# design1.net
KiCad netlist of a schematic drawn in EAGLE
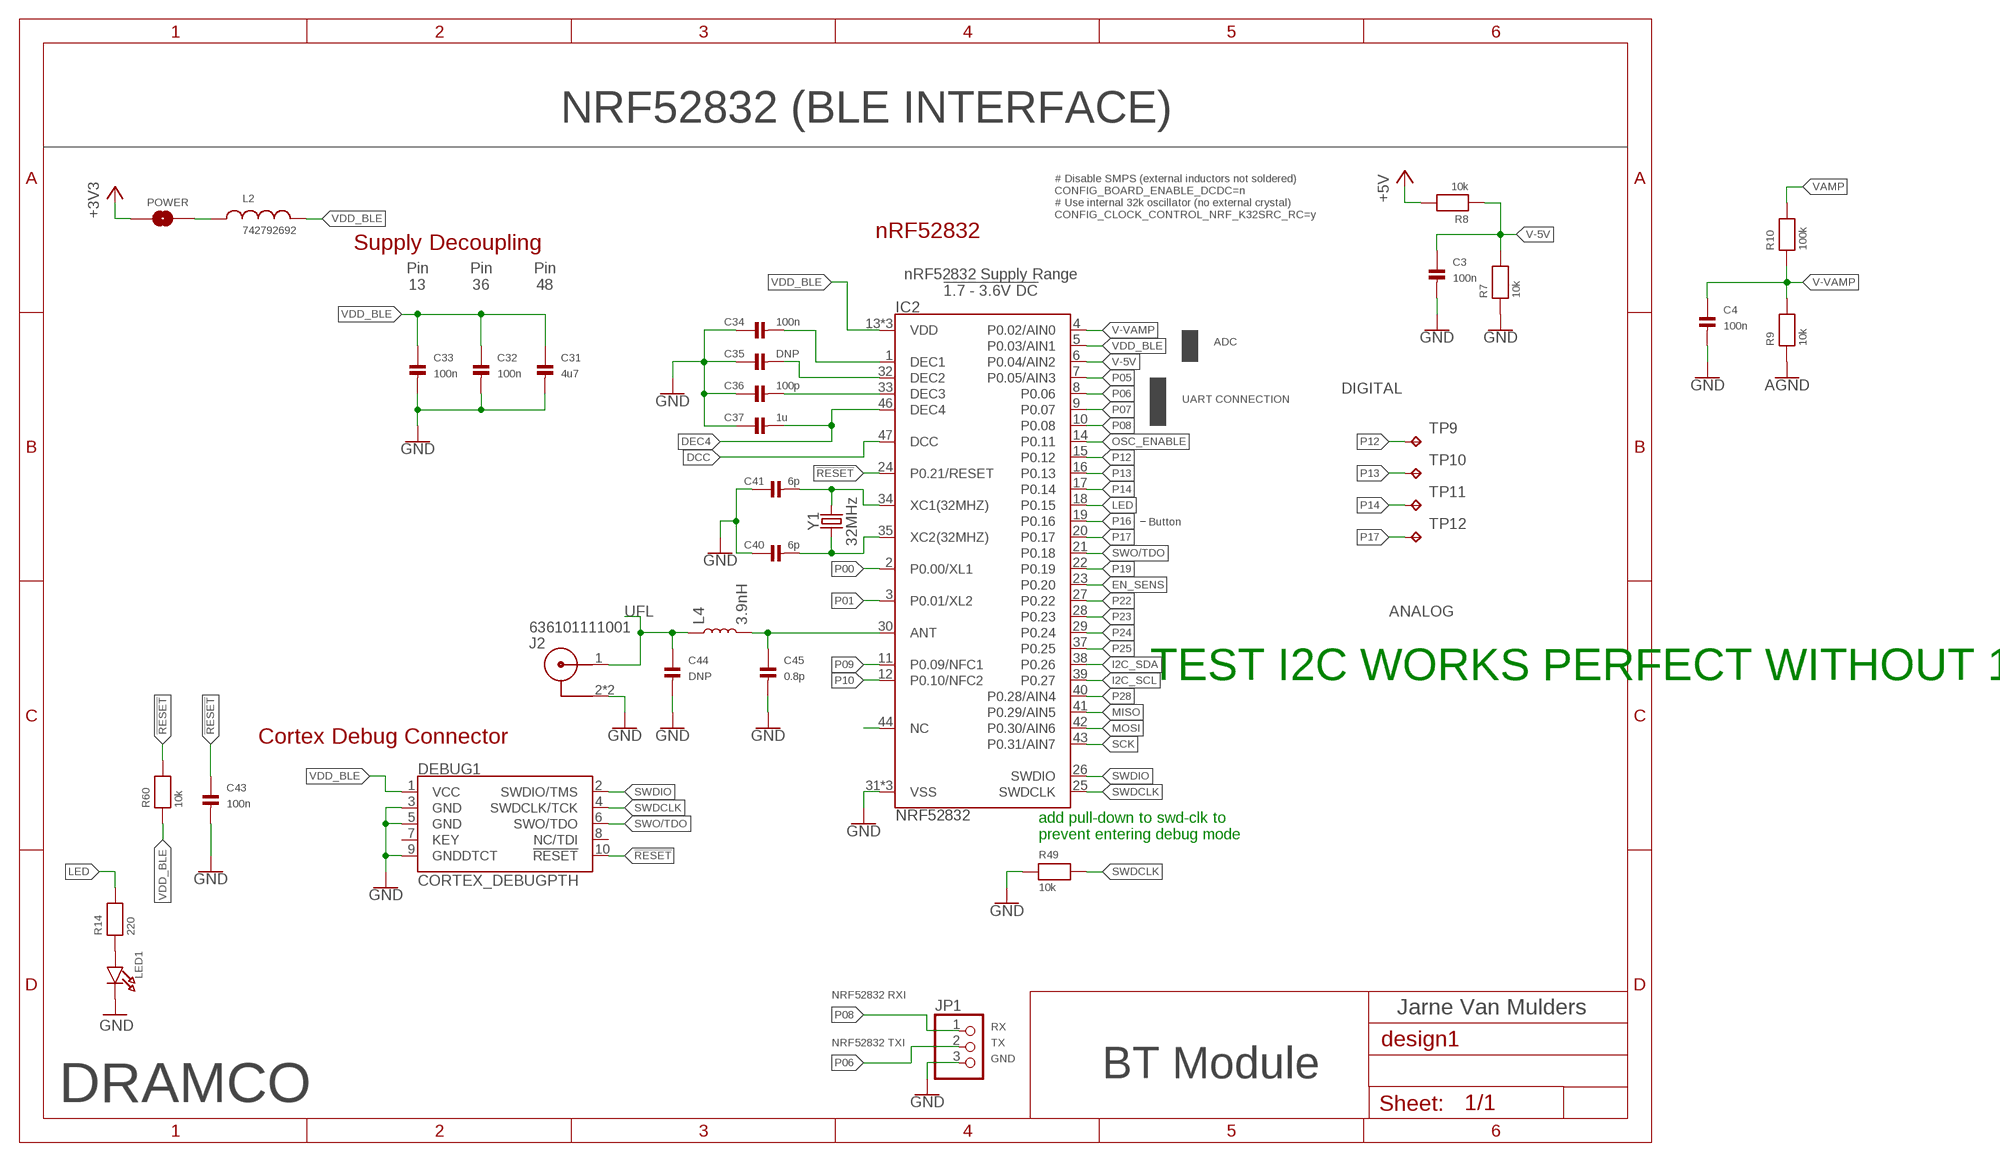
[diagram p0: schematic, sheet 1, part 1 of 2]
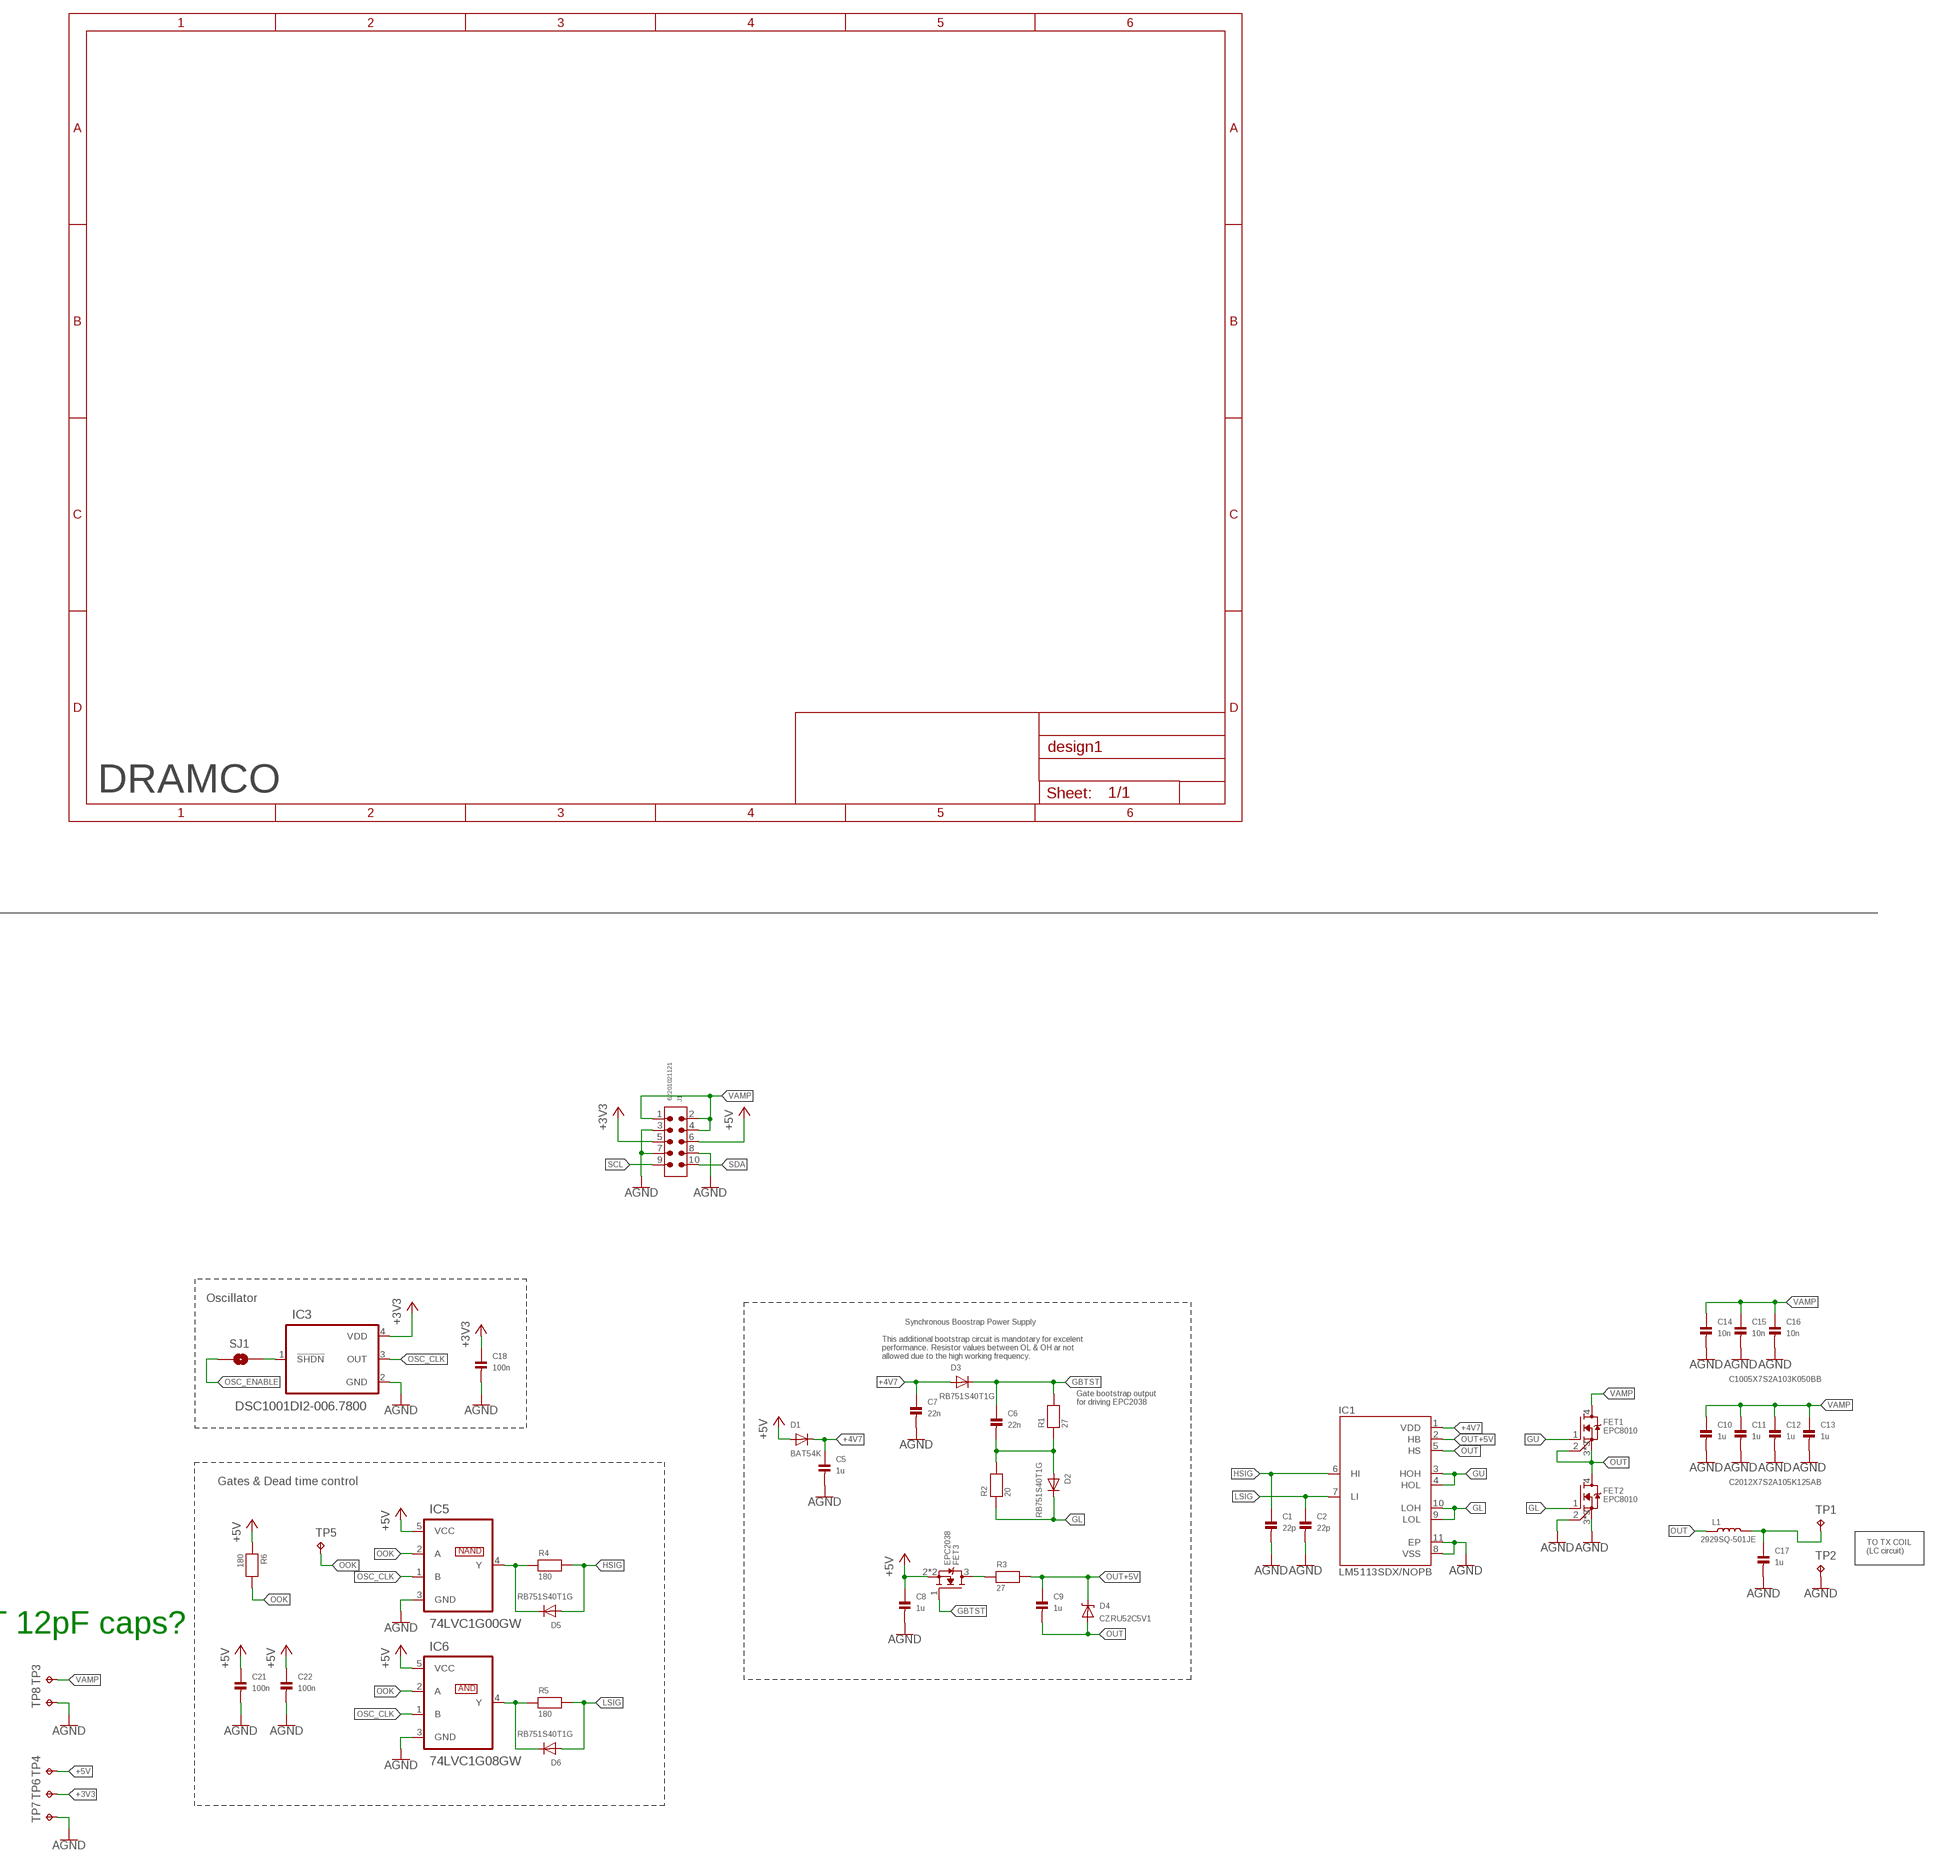
[diagram p1: schematic, sheet 1, part 2 of 2]

(export (version "E")
  (design (tool "Eeschema 10.0.6"))
  (components
    (comp (ref "C1")
      (value "22p")
      (footprint "eagle-import:0402")
      (libsource (lib "eagle-import") (part "CAP_CERAMIC0402"))
    )
    (comp (ref "C2")
      (value "22p")
      (footprint "eagle-import:0402")
      (libsource (lib "eagle-import") (part "CAP_CERAMIC0402"))
    )
    (comp (ref "C3")
      (value "100n")
      (footprint "eagle-import:0402")
      (libsource (lib "eagle-import") (part "CAP_CERAMIC0402"))
    )
    (comp (ref "C4")
      (value "100n")
      (footprint "eagle-import:0402")
      (libsource (lib "eagle-import") (part "CAP_CERAMIC0402"))
    )
    (comp (ref "C5")
      (value "1u")
      (footprint "eagle-import:0402")
      (libsource (lib "eagle-import") (part "CAP_CERAMIC0402"))
    )
    (comp (ref "C6")
      (value "22n")
      (footprint "eagle-import:0402")
      (libsource (lib "eagle-import") (part "CAP_CERAMIC0402"))
    )
    (comp (ref "C7")
      (value "22n")
      (footprint "eagle-import:0402")
      (libsource (lib "eagle-import") (part "CAP_CERAMIC0402"))
    )
    (comp (ref "C8")
      (value "1u")
      (footprint "eagle-import:0402")
      (libsource (lib "eagle-import") (part "CAP_CERAMIC0402"))
    )
    (comp (ref "C9")
      (value "1u")
      (footprint "eagle-import:0402")
      (libsource (lib "eagle-import") (part "CAP_CERAMIC0402"))
    )
    (comp (ref "C10")
      (value "1u")
      (footprint "eagle-import:0805")
      (libsource (lib "eagle-import") (part "CAP_CERAMIC0805"))
    )
    (comp (ref "C11")
      (value "1u")
      (footprint "eagle-import:0805")
      (libsource (lib "eagle-import") (part "CAP_CERAMIC0805"))
    )
    (comp (ref "C12")
      (value "1u")
      (footprint "eagle-import:0805")
      (libsource (lib "eagle-import") (part "CAP_CERAMIC0805"))
    )
    (comp (ref "C13")
      (value "1u")
      (footprint "eagle-import:0805")
      (libsource (lib "eagle-import") (part "CAP_CERAMIC0805"))
    )
    (comp (ref "C14")
      (value "10n")
      (footprint "eagle-import:0402")
      (libsource (lib "eagle-import") (part "CAP_CERAMIC0402"))
    )
    (comp (ref "C15")
      (value "10n")
      (footprint "eagle-import:0402")
      (libsource (lib "eagle-import") (part "CAP_CERAMIC0402"))
    )
    (comp (ref "C16")
      (value "10n")
      (footprint "eagle-import:0402")
      (libsource (lib "eagle-import") (part "CAP_CERAMIC0402"))
    )
    (comp (ref "C17")
      (value "1u")
      (footprint "eagle-import:0805")
      (libsource (lib "eagle-import") (part "CAP_CERAMIC0805"))
    )
    (comp (ref "C18")
      (value "100n")
      (footprint "eagle-import:0603")
      (libsource (lib "eagle-import") (part "CAP_CERAMIC0603"))
    )
    (comp (ref "C21")
      (value "100n")
      (footprint "eagle-import:0402")
      (libsource (lib "eagle-import") (part "CAP_CERAMIC0402"))
    )
    (comp (ref "C22")
      (value "100n")
      (footprint "eagle-import:0402")
      (libsource (lib "eagle-import") (part "CAP_CERAMIC0402"))
    )
    (comp (ref "C31")
      (value "4u7")
      (footprint "eagle-import:0603")
      (libsource (lib "eagle-import") (part "CAP_CERAMIC0603"))
    )
    (comp (ref "C32")
      (value "100n")
      (footprint "eagle-import:0402")
      (libsource (lib "eagle-import") (part "CAP_CERAMIC0402"))
    )
    (comp (ref "C33")
      (value "100n")
      (footprint "eagle-import:0402")
      (libsource (lib "eagle-import") (part "CAP_CERAMIC0402"))
    )
    (comp (ref "C34")
      (value "100n")
      (footprint "eagle-import:0402")
      (libsource (lib "eagle-import") (part "CAP_CERAMIC0402"))
    )
    (comp (ref "C35")
      (value "DNP")
      (footprint "eagle-import:0402")
      (libsource (lib "eagle-import") (part "CAP_CERAMIC0402"))
    )
    (comp (ref "C36")
      (value "100p")
      (footprint "eagle-import:0402")
      (libsource (lib "eagle-import") (part "CAP_CERAMIC0402"))
    )
    (comp (ref "C37")
      (value "1u")
      (footprint "eagle-import:0402")
      (libsource (lib "eagle-import") (part "CAP_CERAMIC0402"))
    )
    (comp (ref "C40")
      (value "6p")
      (footprint "eagle-import:0402")
      (libsource (lib "eagle-import") (part "CAP_CERAMIC0402"))
    )
    (comp (ref "C41")
      (value "6p")
      (footprint "eagle-import:0402")
      (libsource (lib "eagle-import") (part "CAP_CERAMIC0402"))
    )
    (comp (ref "C43")
      (value "100n")
      (footprint "eagle-import:0402")
      (libsource (lib "eagle-import") (part "CAP_CERAMIC0402"))
    )
    (comp (ref "C44")
      (value "DNP")
      (footprint "eagle-import:0402")
      (libsource (lib "eagle-import") (part "CAP_CERAMIC0402"))
    )
    (comp (ref "C45")
      (value "0.8p")
      (footprint "eagle-import:0402")
      (libsource (lib "eagle-import") (part "CAP_CERAMIC0402"))
    )
    (comp (ref "D1")
      (value "BAT54K")
      (footprint "eagle-import:SOD-523")
      (libsource (lib "eagle-import") (part "DIODESOD-523"))
    )
    (comp (ref "D2")
      (value "RB751S40T1G")
      (footprint "eagle-import:SOD-523")
      (libsource (lib "eagle-import") (part "DIODESOD-523"))
    )
    (comp (ref "D3")
      (value "RB751S40T1G")
      (footprint "eagle-import:SOD-523")
      (libsource (lib "eagle-import") (part "DIODESOD-523"))
    )
    (comp (ref "D4")
      (value "CZRU52C5V1")
      (footprint "eagle-import:SOD-523F")
      (libsource (lib "eagle-import") (part "CZRU52"))
    )
    (comp (ref "D5")
      (value "RB751S40T1G")
      (footprint "eagle-import:SOD-523")
      (libsource (lib "eagle-import") (part "DIODESOD-523"))
    )
    (comp (ref "D6")
      (value "RB751S40T1G")
      (footprint "eagle-import:SOD-523")
      (libsource (lib "eagle-import") (part "DIODESOD-523"))
    )
    (comp (ref "DEBUG1")
      (value "CORTEX_DEBUGPTH")
      (footprint "eagle-import:2X5-PTH-1.27MM")
      (libsource (lib "eagle-import") (part "CORTEX_DEBUGPTH"))
    )
    (comp (ref "FET1")
      (value "EPC8010")
      (footprint "eagle-import:BGA-8010")
      (libsource (lib "eagle-import") (part "EPC8010"))
    )
    (comp (ref "FET2")
      (value "EPC8010")
      (footprint "eagle-import:BGA-8010")
      (libsource (lib "eagle-import") (part "EPC8010"))
    )
    (comp (ref "FET3")
      (value "EPC2038")
      (footprint "eagle-import:BGA-2038")
      (libsource (lib "eagle-import") (part "EPC2038"))
    )
    (comp (ref "IC1")
      (value "LM5113SDX/NOPB")
      (footprint "eagle-import:SON80P400X400X80-11N")
      (fields (field (name "MF") "Texas Instruments"))
      (libsource (lib "eagle-import") (part "LM5113SDX/NOPB"))
    )
    (comp (ref "IC2")
      (value "NRF52832")
      (footprint "eagle-import:QFN48-6X6MM-EXTENDED")
      (libsource (lib "eagle-import") (part "NRF52832-EXTENDED"))
    )
    (comp (ref "IC3")
      (value "DSC1001DI2-006.7800")
      (footprint "eagle-import:2.5X2.0MMPLASTICPACKAGE")
      (fields (field (name "MF") "Microchip") (field (name "MP") "DSC1001DI1-025.0000"))
      (libsource (lib "eagle-import") (part "DSC1001DI2-006.7800"))
    )
    (comp (ref "IC5")
      (value "74LVC1G00GW")
      (footprint "eagle-import:SOT65P210X110-5N")
      (fields (field (name "MF") "Nexperia USA"))
      (libsource (lib "eagle-import") (part "74LVC1G00GW"))
    )
    (comp (ref "IC6")
      (value "74LVC1G08GW")
      (footprint "eagle-import:SOT65P210X110-5N")
      (fields (field (name "MF") "Nexperia USA") (field (name "MP") "74LVC1G00GW"))
      (libsource (lib "eagle-import") (part "74LVC1G00GW"))
    )
    (comp (ref "J1")
      (value "62201021121")
      (footprint "eagle-import:62201021121")
      (libsource (lib "eagle-import") (part "6220XX21121_62201021121"))
    )
    (comp (ref "J2")
      (value "636101111001")
      (footprint "eagle-import:636101111001")
      (libsource (lib "eagle-import") (part "636101111001"))
    )
    (comp (ref "JP1")
      (value "HEADER-1X3ROUND")
      (footprint "eagle-import:1X03_ROUND")
      (libsource (lib "eagle-import") (part "HEADER-1X3ROUND"))
    )
    (comp (ref "L1")
      (value "2929SQ-501JE")
      (footprint "eagle-import:2929SQ-501")
      (libsource (lib "eagle-import") (part "2929SQ-501"))
    )
    (comp (ref "L2")
      (value "742792692")
      (footprint "eagle-import:WE-CBF_0603(W=2.2)")
      (libsource (lib "eagle-import") (part "WE-CBF_0603_WB_HS_742792692"))
    )
    (comp (ref "L4")
      (value "3.9nH")
      (footprint "eagle-import:0402")
      (libsource (lib "eagle-import") (part "INDUCTOR-0402-3.9NH"))
    )
    (comp (ref "LED1")
      (value "LED0805")
      (footprint "eagle-import:CHIPLED_0805")
      (libsource (lib "eagle-import") (part "LED0805"))
    )
    (comp (ref "POWER")
      (value "JUMPER-SMT_2_NO_NO-SILK")
      (footprint "eagle-import:SMT-JUMPER_2_NO_NO-SILK")
      (libsource (lib "eagle-import") (part "JUMPER-SMT_2_NO_NO-SILK"))
    )
    (comp (ref "R1")
      (value "27")
      (footprint "eagle-import:0402")
      (libsource (lib "eagle-import") (part "RESISTOR0402"))
    )
    (comp (ref "R2")
      (value "20")
      (footprint "eagle-import:0402")
      (libsource (lib "eagle-import") (part "RESISTOR0402"))
    )
    (comp (ref "R3")
      (value "27")
      (footprint "eagle-import:0402")
      (libsource (lib "eagle-import") (part "RESISTOR0402"))
    )
    (comp (ref "R4")
      (value "180")
      (footprint "eagle-import:0402")
      (libsource (lib "eagle-import") (part "RESISTOR0402"))
    )
    (comp (ref "R5")
      (value "180")
      (footprint "eagle-import:0402")
      (libsource (lib "eagle-import") (part "RESISTOR0402"))
    )
    (comp (ref "R6")
      (value "180")
      (footprint "eagle-import:0402")
      (libsource (lib "eagle-import") (part "RESISTOR0402"))
    )
    (comp (ref "R7")
      (value "10k")
      (footprint "eagle-import:0402")
      (libsource (lib "eagle-import") (part "RESISTOR0402"))
    )
    (comp (ref "R8")
      (value "10k")
      (footprint "eagle-import:0402")
      (libsource (lib "eagle-import") (part "RESISTOR0402"))
    )
    (comp (ref "R9")
      (value "10k")
      (footprint "eagle-import:0402")
      (libsource (lib "eagle-import") (part "RESISTOR0402"))
    )
    (comp (ref "R10")
      (value "100k")
      (footprint "eagle-import:0402")
      (libsource (lib "eagle-import") (part "RESISTOR0402"))
    )
    (comp (ref "R14")
      (value "220")
      (footprint "eagle-import:0603")
      (libsource (lib "eagle-import") (part "RESISTOR0603"))
    )
    (comp (ref "R49")
      (value "10k")
      (footprint "eagle-import:0402")
      (libsource (lib "eagle-import") (part "RESISTOR0402"))
    )
    (comp (ref "R60")
      (value "10k")
      (footprint "eagle-import:0402")
      (libsource (lib "eagle-import") (part "RESISTOR0402"))
    )
    (comp (ref "SJ1")
      (value "SOLDERJUMPERNO")
      (footprint "eagle-import:SJ_2S-NO")
      (libsource (lib "eagle-import") (part "SOLDERJUMPERNO"))
    )
    (comp (ref "TP1")
      (value "TPTP20SQ")
      (footprint "eagle-import:TP20SQ")
      (libsource (lib "eagle-import") (part "TPTP20SQ"))
    )
    (comp (ref "TP2")
      (value "TPTP20SQ")
      (footprint "eagle-import:TP20SQ")
      (libsource (lib "eagle-import") (part "TPTP20SQ"))
    )
    (comp (ref "TP3")
      (value "TPTP20SQ")
      (footprint "eagle-import:TP20SQ")
      (libsource (lib "eagle-import") (part "TPTP20SQ"))
    )
    (comp (ref "TP4")
      (value "TPTP10SQ")
      (footprint "eagle-import:TP10SQ")
      (libsource (lib "eagle-import") (part "TPTP10SQ"))
    )
    (comp (ref "TP5")
      (value "TPTP10SQ")
      (footprint "eagle-import:TP10SQ")
      (libsource (lib "eagle-import") (part "TPTP10SQ"))
    )
    (comp (ref "TP6")
      (value "TPTP10SQ")
      (footprint "eagle-import:TP10SQ")
      (libsource (lib "eagle-import") (part "TPTP10SQ"))
    )
    (comp (ref "TP7")
      (value "TPTP10SQ")
      (footprint "eagle-import:TP10SQ")
      (libsource (lib "eagle-import") (part "TPTP10SQ"))
    )
    (comp (ref "TP8")
      (value "TPTP20SQ")
      (footprint "eagle-import:TP20SQ")
      (libsource (lib "eagle-import") (part "TPTP20SQ"))
    )
    (comp (ref "TP9")
      (value "TPTP10SQ")
      (footprint "eagle-import:TP10SQ")
      (libsource (lib "eagle-import") (part "TPTP10SQ"))
    )
    (comp (ref "TP10")
      (value "TPTP10SQ")
      (footprint "eagle-import:TP10SQ")
      (libsource (lib "eagle-import") (part "TPTP10SQ"))
    )
    (comp (ref "TP11")
      (value "TPTP10SQ")
      (footprint "eagle-import:TP10SQ")
      (libsource (lib "eagle-import") (part "TPTP10SQ"))
    )
    (comp (ref "TP12")
      (value "TPTP10SQ")
      (footprint "eagle-import:TP10SQ")
      (libsource (lib "eagle-import") (part "TPTP10SQ"))
    )
    (comp (ref "Y1")
      (value "32MHz")
      (footprint "eagle-import:CRYSTAL-SMD-2.0X1.6MM")
      (libsource (lib "eagle-import") (part "CRYSTAL-32MHZ-SMD-2.0X1.6MM"))
    )
  )
  (nets
    (net (code "1") (name "+3V3") (class "Default")
      (node (ref "C18") (pin "1") (pinfunction "P$1_1") (pintype "passive"))
      (node (ref "IC3") (pin "4") (pinfunction "VDD_4") (pintype "power_in"))
      (node (ref "J1") (pin "5") (pinfunction "5_5") (pintype "passive"))
      (node (ref "POWER") (pin "1") (pinfunction "1_1") (pintype "passive"))
      (node (ref "TP6") (pin "TP") (pinfunction "TP_TP") (pintype "input"))
    )
    (net (code "2") (name "+4V7") (class "Default")
      (node (ref "C5") (pin "1") (pinfunction "P$1_1") (pintype "passive"))
      (node (ref "C7") (pin "1") (pinfunction "P$1_1") (pintype "passive"))
      (node (ref "D1") (pin "K") (pinfunction "C_K") (pintype "passive"))
      (node (ref "D3") (pin "A") (pinfunction "A_A") (pintype "passive"))
      (node (ref "IC1") (pin "1") (pinfunction "VDD_1") (pintype "power_in"))
    )
    (net (code "3") (name "+5V") (class "Default")
      (node (ref "C21") (pin "1") (pinfunction "P$1_1") (pintype "passive"))
      (node (ref "C22") (pin "1") (pinfunction "P$1_1") (pintype "passive"))
      (node (ref "C8") (pin "1") (pinfunction "P$1_1") (pintype "passive"))
      (node (ref "D1") (pin "A") (pinfunction "A_A") (pintype "passive"))
      (node (ref "FET3") (pin "2") (pinfunction "S_2") (pintype "bidirectional"))
      (node (ref "FET3") (pin "4") (pinfunction "S_4") (pintype "bidirectional"))
      (node (ref "IC5") (pin "5") (pinfunction "VCC_5") (pintype "power_in"))
      (node (ref "IC6") (pin "5") (pinfunction "VCC_5") (pintype "power_in"))
      (node (ref "J1") (pin "6") (pinfunction "6_6") (pintype "passive"))
      (node (ref "R6") (pin "1") (pinfunction "1_1") (pintype "passive"))
      (node (ref "R8") (pin "2") (pinfunction "2_2") (pintype "passive"))
      (node (ref "TP4") (pin "TP") (pinfunction "TP_TP") (pintype "input"))
    )
    (net (code "4") (name "/UFL") (class "Default")
      (node (ref "C44") (pin "1") (pinfunction "P$1_1") (pintype "passive"))
      (node (ref "J2") (pin "1") (pinfunction "1_1") (pintype "passive"))
      (node (ref "L4") (pin "1") (pinfunction "1_1") (pintype "passive"))
    )
    (net (code "5") (name "/~{RESET}") (class "Default")
      (node (ref "C43") (pin "1") (pinfunction "P$1_1") (pintype "passive"))
      (node (ref "DEBUG1") (pin "10") (pinfunction "~{RESET}_10") (pintype "bidirectional"))
      (node (ref "IC2") (pin "24") (pinfunction "P0.21/RESET_24") (pintype "bidirectional"))
      (node (ref "R60") (pin "2") (pinfunction "2_2") (pintype "passive"))
    )
    (net (code "6") (name "AGND") (class "Default")
      (node (ref "C1") (pin "2") (pinfunction "P$2_2") (pintype "passive"))
      (node (ref "C10") (pin "2") (pinfunction "P$2_2") (pintype "passive"))
      (node (ref "C11") (pin "2") (pinfunction "P$2_2") (pintype "passive"))
      (node (ref "C12") (pin "2") (pinfunction "P$2_2") (pintype "passive"))
      (node (ref "C13") (pin "2") (pinfunction "P$2_2") (pintype "passive"))
      (node (ref "C14") (pin "2") (pinfunction "P$2_2") (pintype "passive"))
      (node (ref "C15") (pin "2") (pinfunction "P$2_2") (pintype "passive"))
      (node (ref "C16") (pin "2") (pinfunction "P$2_2") (pintype "passive"))
      (node (ref "C17") (pin "2") (pinfunction "P$2_2") (pintype "passive"))
      (node (ref "C18") (pin "2") (pinfunction "P$2_2") (pintype "passive"))
      (node (ref "C2") (pin "2") (pinfunction "P$2_2") (pintype "passive"))
      (node (ref "C21") (pin "2") (pinfunction "P$2_2") (pintype "passive"))
      (node (ref "C22") (pin "2") (pinfunction "P$2_2") (pintype "passive"))
      (node (ref "C5") (pin "2") (pinfunction "P$2_2") (pintype "passive"))
      (node (ref "C7") (pin "2") (pinfunction "P$2_2") (pintype "passive"))
      (node (ref "C8") (pin "2") (pinfunction "P$2_2") (pintype "passive"))
      (node (ref "FET2") (pin "2") (pinfunction "SR_2") (pintype "bidirectional"))
      (node (ref "FET2") (pin "3") (pinfunction "S_3") (pintype "bidirectional"))
      (node (ref "FET2") (pin "5") (pinfunction "S_5") (pintype "bidirectional"))
      (node (ref "FET2") (pin "6") (pinfunction "S_6") (pintype "bidirectional"))
      (node (ref "IC1") (pin "11") (pinfunction "EP_11") (pintype "power_in"))
      (node (ref "IC1") (pin "8") (pinfunction "VSS_8") (pintype "power_in"))
      (node (ref "IC3") (pin "2") (pinfunction "GND_2") (pintype "power_in"))
      (node (ref "IC5") (pin "3") (pinfunction "GND_3") (pintype "passive"))
      (node (ref "IC6") (pin "3") (pinfunction "GND_3") (pintype "passive"))
      (node (ref "J1") (pin "3") (pinfunction "3_3") (pintype "passive"))
      (node (ref "J1") (pin "7") (pinfunction "7_7") (pintype "passive"))
      (node (ref "J1") (pin "8") (pinfunction "8_8") (pintype "passive"))
      (node (ref "R9") (pin "1") (pinfunction "1_1") (pintype "passive"))
      (node (ref "TP2") (pin "TP") (pinfunction "TP_TP") (pintype "input"))
      (node (ref "TP7") (pin "TP") (pinfunction "TP_TP") (pintype "input"))
      (node (ref "TP8") (pin "TP") (pinfunction "TP_TP") (pintype "input"))
    )
    (net (code "7") (name "DCC") (class "Default")
      (node (ref "IC2") (pin "47") (pinfunction "DCC_47") (pintype "bidirectional"))
    )
    (net (code "8") (name "DEC4") (class "Default")
      (node (ref "C37") (pin "2") (pinfunction "P$2_2") (pintype "passive"))
      (node (ref "IC2") (pin "46") (pinfunction "DEC4_46") (pintype "bidirectional"))
    )
    (net (code "9") (name "EN_SENS") (class "Default")
      (node (ref "IC2") (pin "23") (pinfunction "P0.20_23") (pintype "bidirectional"))
    )
    (net (code "10") (name "GBTST") (class "Default")
      (node (ref "C6") (pin "1") (pinfunction "P$1_1") (pintype "passive"))
      (node (ref "D3") (pin "K") (pinfunction "C_K") (pintype "passive"))
      (node (ref "FET3") (pin "1") (pinfunction "G_1") (pintype "bidirectional"))
      (node (ref "R1") (pin "2") (pinfunction "2_2") (pintype "passive"))
    )
    (net (code "11") (name "GL") (class "Default")
      (node (ref "D2") (pin "K") (pinfunction "C_K") (pintype "passive"))
      (node (ref "FET2") (pin "1") (pinfunction "G_1") (pintype "bidirectional"))
      (node (ref "IC1") (pin "10") (pinfunction "LOH_10") (pintype "output"))
      (node (ref "IC1") (pin "9") (pinfunction "LOL_9") (pintype "output"))
      (node (ref "R2") (pin "1") (pinfunction "1_1") (pintype "passive"))
    )
    (net (code "12") (name "GND") (class "Default")
      (node (ref "C3") (pin "2") (pinfunction "P$2_2") (pintype "passive"))
      (node (ref "C31") (pin "2") (pinfunction "P$2_2") (pintype "passive"))
      (node (ref "C32") (pin "2") (pinfunction "P$2_2") (pintype "passive"))
      (node (ref "C33") (pin "2") (pinfunction "P$2_2") (pintype "passive"))
      (node (ref "C34") (pin "1") (pinfunction "P$1_1") (pintype "passive"))
      (node (ref "C35") (pin "1") (pinfunction "P$1_1") (pintype "passive"))
      (node (ref "C36") (pin "1") (pinfunction "P$1_1") (pintype "passive"))
      (node (ref "C37") (pin "1") (pinfunction "P$1_1") (pintype "passive"))
      (node (ref "C4") (pin "2") (pinfunction "P$2_2") (pintype "passive"))
      (node (ref "C40") (pin "1") (pinfunction "P$1_1") (pintype "passive"))
      (node (ref "C41") (pin "1") (pinfunction "P$1_1") (pintype "passive"))
      (node (ref "C43") (pin "2") (pinfunction "P$2_2") (pintype "passive"))
      (node (ref "C44") (pin "2") (pinfunction "P$2_2") (pintype "passive"))
      (node (ref "C45") (pin "2") (pinfunction "P$2_2") (pintype "passive"))
      (node (ref "DEBUG1") (pin "3") (pinfunction "GND_3") (pintype "bidirectional"))
      (node (ref "DEBUG1") (pin "5") (pinfunction "GND_5") (pintype "bidirectional"))
      (node (ref "DEBUG1") (pin "9") (pinfunction "GNDDTCT_9") (pintype "bidirectional"))
      (node (ref "IC2") (pin "31") (pinfunction "VSS_31") (pintype "bidirectional"))
      (node (ref "IC2") (pin "45") (pinfunction "VSS_45") (pintype "bidirectional"))
      (node (ref "IC2") (pin "EP") (pinfunction "VSS_EP") (pintype "bidirectional"))
      (node (ref "J2") (pin "2") (pinfunction "2_2") (pintype "passive"))
      (node (ref "J2") (pin "3") (pinfunction "2_3") (pintype "passive"))
      (node (ref "JP1") (pin "3") (pinfunction "3_3") (pintype "passive"))
      (node (ref "LED1") (pin "C") (pinfunction "C_C") (pintype "passive"))
      (node (ref "R49") (pin "1") (pinfunction "1_1") (pintype "passive"))
      (node (ref "R7") (pin "1") (pinfunction "1_1") (pintype "passive"))
    )
    (net (code "13") (name "GU") (class "Default")
      (node (ref "FET1") (pin "1") (pinfunction "G_1") (pintype "bidirectional"))
      (node (ref "IC1") (pin "3") (pinfunction "HOH_3") (pintype "output"))
      (node (ref "IC1") (pin "4") (pinfunction "HOL_4") (pintype "output"))
    )
    (net (code "14") (name "HSIG") (class "Default")
      (node (ref "C1") (pin "1") (pinfunction "P$1_1") (pintype "passive"))
      (node (ref "D5") (pin "A") (pinfunction "A_A") (pintype "passive"))
      (node (ref "IC1") (pin "6") (pinfunction "HI_6") (pintype "input"))
      (node (ref "R4") (pin "2") (pinfunction "2_2") (pintype "passive"))
    )
    (net (code "15") (name "I2C_SCL") (class "Default")
      (node (ref "IC2") (pin "39") (pinfunction "P0.27_39") (pintype "bidirectional"))
    )
    (net (code "16") (name "I2C_SDA") (class "Default")
      (node (ref "IC2") (pin "38") (pinfunction "P0.26_38") (pintype "bidirectional"))
    )
    (net (code "17") (name "LED") (class "Default")
      (node (ref "IC2") (pin "18") (pinfunction "P0.15_18") (pintype "bidirectional"))
      (node (ref "R14") (pin "2") (pinfunction "2_2") (pintype "passive"))
    )
    (net (code "18") (name "LSIG") (class "Default")
      (node (ref "C2") (pin "1") (pinfunction "P$1_1") (pintype "passive"))
      (node (ref "D6") (pin "A") (pinfunction "A_A") (pintype "passive"))
      (node (ref "IC1") (pin "7") (pinfunction "LI_7") (pintype "input"))
      (node (ref "R5") (pin "2") (pinfunction "2_2") (pintype "passive"))
    )
    (net (code "19") (name "MISO") (class "Default")
      (node (ref "IC2") (pin "41") (pinfunction "P0.29/AIN5_41") (pintype "bidirectional"))
    )
    (net (code "20") (name "MOSI") (class "Default")
      (node (ref "IC2") (pin "42") (pinfunction "P0.30/AIN6_42") (pintype "bidirectional"))
    )
    (net (code "21") (name "Net-(C6-P$2)") (class "Default")
      (node (ref "C6") (pin "2") (pinfunction "P$2_2") (pintype "passive"))
      (node (ref "D2") (pin "A") (pinfunction "A_A") (pintype "passive"))
      (node (ref "R1") (pin "1") (pinfunction "1_1") (pintype "passive"))
      (node (ref "R2") (pin "2") (pinfunction "2_2") (pintype "passive"))
    )
    (net (code "22") (name "Net-(C17-P$1)") (class "Default")
      (node (ref "C17") (pin "1") (pinfunction "P$1_1") (pintype "passive"))
      (node (ref "L1") (pin "2") (pinfunction "2_2") (pintype "bidirectional"))
      (node (ref "TP1") (pin "TP") (pinfunction "TP_TP") (pintype "input"))
    )
    (net (code "23") (name "Net-(C34-P$2)") (class "Default")
      (node (ref "C34") (pin "2") (pinfunction "P$2_2") (pintype "passive"))
      (node (ref "IC2") (pin "1") (pinfunction "DEC1_1") (pintype "bidirectional"))
    )
    (net (code "24") (name "Net-(C35-P$2)") (class "Default")
      (node (ref "C35") (pin "2") (pinfunction "P$2_2") (pintype "passive"))
      (node (ref "IC2") (pin "32") (pinfunction "DEC2_32") (pintype "bidirectional"))
    )
    (net (code "25") (name "Net-(C36-P$2)") (class "Default")
      (node (ref "C36") (pin "2") (pinfunction "P$2_2") (pintype "passive"))
      (node (ref "IC2") (pin "33") (pinfunction "DEC3_33") (pintype "bidirectional"))
    )
    (net (code "26") (name "Net-(C40-P$2)") (class "Default")
      (node (ref "C40") (pin "2") (pinfunction "P$2_2") (pintype "passive"))
      (node (ref "IC2") (pin "35") (pinfunction "XC2(32MHZ)_35") (pintype "bidirectional"))
      (node (ref "Y1") (pin "1") (pinfunction "1_1") (pintype "passive"))
    )
    (net (code "27") (name "Net-(C41-P$2)") (class "Default")
      (node (ref "C41") (pin "2") (pinfunction "P$2_2") (pintype "passive"))
      (node (ref "IC2") (pin "34") (pinfunction "XC1(32MHZ)_34") (pintype "bidirectional"))
      (node (ref "Y1") (pin "3") (pinfunction "2_3") (pintype "passive"))
    )
    (net (code "28") (name "Net-(C45-P$1)") (class "Default")
      (node (ref "C45") (pin "1") (pinfunction "P$1_1") (pintype "passive"))
      (node (ref "IC2") (pin "30") (pinfunction "ANT_30") (pintype "bidirectional"))
      (node (ref "L4") (pin "2") (pinfunction "2_2") (pintype "passive"))
    )
    (net (code "29") (name "Net-(D5-C)") (class "Default")
      (node (ref "D5") (pin "K") (pinfunction "C_K") (pintype "passive"))
      (node (ref "IC5") (pin "4") (pinfunction "Y_4") (pintype "output"))
      (node (ref "R4") (pin "1") (pinfunction "1_1") (pintype "passive"))
    )
    (net (code "30") (name "Net-(D6-C)") (class "Default")
      (node (ref "D6") (pin "K") (pinfunction "C_K") (pintype "passive"))
      (node (ref "IC6") (pin "4") (pinfunction "Y_4") (pintype "output"))
      (node (ref "R5") (pin "1") (pinfunction "1_1") (pintype "passive"))
    )
    (net (code "31") (name "Net-(FET3-D)") (class "Default")
      (node (ref "FET3") (pin "3") (pinfunction "D_3") (pintype "bidirectional"))
      (node (ref "R3") (pin "1") (pinfunction "1_1") (pintype "passive"))
    )
    (net (code "32") (name "Net-(IC3-~{SHDN})") (class "Default")
      (node (ref "IC3") (pin "1") (pinfunction "~{SHDN}_1") (pintype "input"))
      (node (ref "SJ1") (pin "2") (pinfunction "2_2") (pintype "passive"))
    )
    (net (code "33") (name "Net-(L2-Pad1)") (class "Default")
      (node (ref "L2") (pin "1") (pinfunction "1_1") (pintype "passive"))
      (node (ref "POWER") (pin "2") (pinfunction "2_2") (pintype "passive"))
    )
    (net (code "34") (name "Net-(LED1-PadA)") (class "Default")
      (node (ref "LED1") (pin "A") (pinfunction "A_A") (pintype "passive"))
      (node (ref "R14") (pin "1") (pinfunction "1_1") (pintype "passive"))
    )
    (net (code "35") (name "OOK") (class "Default")
      (node (ref "IC5") (pin "2") (pinfunction "A_2") (pintype "input"))
      (node (ref "IC6") (pin "2") (pinfunction "A_2") (pintype "input"))
      (node (ref "R6") (pin "2") (pinfunction "2_2") (pintype "passive"))
      (node (ref "TP5") (pin "TP") (pinfunction "TP_TP") (pintype "input"))
    )
    (net (code "36") (name "OSC_CLK") (class "Default")
      (node (ref "IC3") (pin "3") (pinfunction "OUT_3") (pintype "output"))
      (node (ref "IC5") (pin "1") (pinfunction "B_1") (pintype "input"))
      (node (ref "IC6") (pin "1") (pinfunction "B_1") (pintype "input"))
    )
    (net (code "37") (name "OSC_ENABLE") (class "Default")
      (node (ref "IC2") (pin "14") (pinfunction "P0.11_14") (pintype "bidirectional"))
      (node (ref "SJ1") (pin "1") (pinfunction "1_1") (pintype "passive"))
    )
    (net (code "38") (name "OUT") (class "Default")
      (node (ref "C9") (pin "2") (pinfunction "P$2_2") (pintype "passive"))
      (node (ref "D4") (pin "2") (pinfunction "A_2") (pintype "passive"))
      (node (ref "FET1") (pin "2") (pinfunction "SR_2") (pintype "bidirectional"))
      (node (ref "FET1") (pin "3") (pinfunction "S_3") (pintype "bidirectional"))
      (node (ref "FET1") (pin "5") (pinfunction "S_5") (pintype "bidirectional"))
      (node (ref "FET1") (pin "6") (pinfunction "S_6") (pintype "bidirectional"))
      (node (ref "FET2") (pin "4") (pinfunction "D_4") (pintype "bidirectional"))
      (node (ref "IC1") (pin "5") (pinfunction "HS_5") (pintype "power_in"))
      (node (ref "L1") (pin "1") (pinfunction "1_1") (pintype "bidirectional"))
    )
    (net (code "39") (name "OUT+5V") (class "Default")
      (node (ref "C9") (pin "1") (pinfunction "P$1_1") (pintype "passive"))
      (node (ref "D4") (pin "1") (pinfunction "C_1") (pintype "passive"))
      (node (ref "IC1") (pin "2") (pinfunction "HB_2") (pintype "power_in"))
      (node (ref "R3") (pin "2") (pinfunction "2_2") (pintype "passive"))
    )
    (net (code "40") (name "P00") (class "Default")
      (node (ref "IC2") (pin "2") (pinfunction "P0.00/XL1_2") (pintype "bidirectional"))
    )
    (net (code "41") (name "P01") (class "Default")
      (node (ref "IC2") (pin "3") (pinfunction "P0.01/XL2_3") (pintype "bidirectional"))
    )
    (net (code "42") (name "P05") (class "Default")
      (node (ref "IC2") (pin "7") (pinfunction "P0.05/AIN3_7") (pintype "bidirectional"))
    )
    (net (code "43") (name "P06") (class "Default")
      (node (ref "IC2") (pin "8") (pinfunction "P0.06_8") (pintype "bidirectional"))
      (node (ref "JP1") (pin "2") (pinfunction "2_2") (pintype "passive"))
    )
    (net (code "44") (name "P07") (class "Default")
      (node (ref "IC2") (pin "9") (pinfunction "P0.07_9") (pintype "bidirectional"))
    )
    (net (code "45") (name "P08") (class "Default")
      (node (ref "IC2") (pin "10") (pinfunction "P0.08_10") (pintype "bidirectional"))
      (node (ref "JP1") (pin "1") (pinfunction "1_1") (pintype "passive"))
    )
    (net (code "46") (name "P09") (class "Default")
      (node (ref "IC2") (pin "11") (pinfunction "P0.09/NFC1_11") (pintype "bidirectional"))
    )
    (net (code "47") (name "P10") (class "Default")
      (node (ref "IC2") (pin "12") (pinfunction "P0.10/NFC2_12") (pintype "bidirectional"))
    )
    (net (code "48") (name "P12") (class "Default")
      (node (ref "IC2") (pin "15") (pinfunction "P0.12_15") (pintype "bidirectional"))
      (node (ref "TP9") (pin "TP") (pinfunction "TP_TP") (pintype "input"))
    )
    (net (code "49") (name "P13") (class "Default")
      (node (ref "IC2") (pin "16") (pinfunction "P0.13_16") (pintype "bidirectional"))
      (node (ref "TP10") (pin "TP") (pinfunction "TP_TP") (pintype "input"))
    )
    (net (code "50") (name "P14") (class "Default")
      (node (ref "IC2") (pin "17") (pinfunction "P0.14_17") (pintype "bidirectional"))
      (node (ref "TP11") (pin "TP") (pinfunction "TP_TP") (pintype "input"))
    )
    (net (code "51") (name "P16") (class "Default")
      (node (ref "IC2") (pin "19") (pinfunction "P0.16_19") (pintype "bidirectional"))
    )
    (net (code "52") (name "P17") (class "Default")
      (node (ref "IC2") (pin "20") (pinfunction "P0.17_20") (pintype "bidirectional"))
      (node (ref "TP12") (pin "TP") (pinfunction "TP_TP") (pintype "input"))
    )
    (net (code "53") (name "P19") (class "Default")
      (node (ref "IC2") (pin "22") (pinfunction "P0.19_22") (pintype "bidirectional"))
    )
    (net (code "54") (name "P22") (class "Default")
      (node (ref "IC2") (pin "27") (pinfunction "P0.22_27") (pintype "bidirectional"))
    )
    (net (code "55") (name "P23") (class "Default")
      (node (ref "IC2") (pin "28") (pinfunction "P0.23_28") (pintype "bidirectional"))
    )
    (net (code "56") (name "P24") (class "Default")
      (node (ref "IC2") (pin "29") (pinfunction "P0.24_29") (pintype "bidirectional"))
    )
    (net (code "57") (name "P25") (class "Default")
      (node (ref "IC2") (pin "37") (pinfunction "P0.25_37") (pintype "bidirectional"))
    )
    (net (code "58") (name "P28") (class "Default")
      (node (ref "IC2") (pin "40") (pinfunction "P0.28/AIN4_40") (pintype "bidirectional"))
    )
    (net (code "59") (name "SCK") (class "Default")
      (node (ref "IC2") (pin "43") (pinfunction "P0.31/AIN7_43") (pintype "bidirectional"))
    )
    (net (code "60") (name "SCL") (class "Default")
      (node (ref "J1") (pin "9") (pinfunction "9_9") (pintype "passive"))
    )
    (net (code "61") (name "SDA") (class "Default")
      (node (ref "J1") (pin "10") (pinfunction "10_10") (pintype "passive"))
    )
    (net (code "62") (name "SWDCLK") (class "Default")
      (node (ref "DEBUG1") (pin "4") (pinfunction "SWDCLK/TCK_4") (pintype "bidirectional"))
      (node (ref "IC2") (pin "25") (pinfunction "SWDCLK_25") (pintype "bidirectional"))
      (node (ref "R49") (pin "2") (pinfunction "2_2") (pintype "passive"))
    )
    (net (code "63") (name "SWDIO") (class "Default")
      (node (ref "DEBUG1") (pin "2") (pinfunction "SWDIO/TMS_2") (pintype "bidirectional"))
      (node (ref "IC2") (pin "26") (pinfunction "SWDIO_26") (pintype "bidirectional"))
    )
    (net (code "64") (name "SWO{slash}TDO") (class "Default")
      (node (ref "DEBUG1") (pin "6") (pinfunction "SWO/TDO_6") (pintype "bidirectional"))
      (node (ref "IC2") (pin "21") (pinfunction "P0.18_21") (pintype "bidirectional"))
    )
    (net (code "65") (name "V-5V") (class "Default")
      (node (ref "C3") (pin "1") (pinfunction "P$1_1") (pintype "passive"))
      (node (ref "IC2") (pin "6") (pinfunction "P0.04/AIN2_6") (pintype "bidirectional"))
      (node (ref "R7") (pin "2") (pinfunction "2_2") (pintype "passive"))
      (node (ref "R8") (pin "1") (pinfunction "1_1") (pintype "passive"))
    )
    (net (code "66") (name "V-VAMP") (class "Default")
      (node (ref "C4") (pin "1") (pinfunction "P$1_1") (pintype "passive"))
      (node (ref "IC2") (pin "4") (pinfunction "P0.02/AIN0_4") (pintype "bidirectional"))
      (node (ref "R10") (pin "1") (pinfunction "1_1") (pintype "passive"))
      (node (ref "R9") (pin "2") (pinfunction "2_2") (pintype "passive"))
    )
    (net (code "67") (name "VAMP") (class "Default")
      (node (ref "C10") (pin "1") (pinfunction "P$1_1") (pintype "passive"))
      (node (ref "C11") (pin "1") (pinfunction "P$1_1") (pintype "passive"))
      (node (ref "C12") (pin "1") (pinfunction "P$1_1") (pintype "passive"))
      (node (ref "C13") (pin "1") (pinfunction "P$1_1") (pintype "passive"))
      (node (ref "C14") (pin "1") (pinfunction "P$1_1") (pintype "passive"))
      (node (ref "C15") (pin "1") (pinfunction "P$1_1") (pintype "passive"))
      (node (ref "C16") (pin "1") (pinfunction "P$1_1") (pintype "passive"))
      (node (ref "FET1") (pin "4") (pinfunction "D_4") (pintype "bidirectional"))
      (node (ref "J1") (pin "1") (pinfunction "1_1") (pintype "passive"))
      (node (ref "J1") (pin "2") (pinfunction "2_2") (pintype "passive"))
      (node (ref "J1") (pin "4") (pinfunction "4_4") (pintype "passive"))
      (node (ref "R10") (pin "2") (pinfunction "2_2") (pintype "passive"))
      (node (ref "TP3") (pin "TP") (pinfunction "TP_TP") (pintype "input"))
    )
    (net (code "68") (name "VDD_BLE") (class "Default")
      (node (ref "C31") (pin "1") (pinfunction "P$1_1") (pintype "passive"))
      (node (ref "C32") (pin "1") (pinfunction "P$1_1") (pintype "passive"))
      (node (ref "C33") (pin "1") (pinfunction "P$1_1") (pintype "passive"))
      (node (ref "DEBUG1") (pin "1") (pinfunction "VCC_1") (pintype "bidirectional"))
      (node (ref "IC2") (pin "13") (pinfunction "VDD_13") (pintype "bidirectional"))
      (node (ref "IC2") (pin "36") (pinfunction "VDD_36") (pintype "bidirectional"))
      (node (ref "IC2") (pin "48") (pinfunction "VDD_48") (pintype "bidirectional"))
      (node (ref "IC2") (pin "5") (pinfunction "P0.03/AIN1_5") (pintype "bidirectional"))
      (node (ref "L2") (pin "2") (pinfunction "2_2") (pintype "passive"))
      (node (ref "R60") (pin "1") (pinfunction "1_1") (pintype "passive"))
    )
    (net (code "69") (name "unconnected-(DEBUG1-KEY-Pad7)") (class "Default")
      (node (ref "DEBUG1") (pin "7") (pinfunction "KEY_7") (pintype "bidirectional"))
    )
    (net (code "70") (name "unconnected-(DEBUG1-NC{slash}TDI-Pad8)") (class "Default")
      (node (ref "DEBUG1") (pin "8") (pinfunction "NC/TDI_8") (pintype "bidirectional"))
    )
    (net (code "71") (name "unconnected-(IC2-NC-Pad44)") (class "Default")
      (node (ref "IC2") (pin "44") (pinfunction "NC_44") (pintype "bidirectional"))
    )
  )
)
